# Mikrolysreklamen.net
KiCad netlist of a schematic drawn in Altium Designer
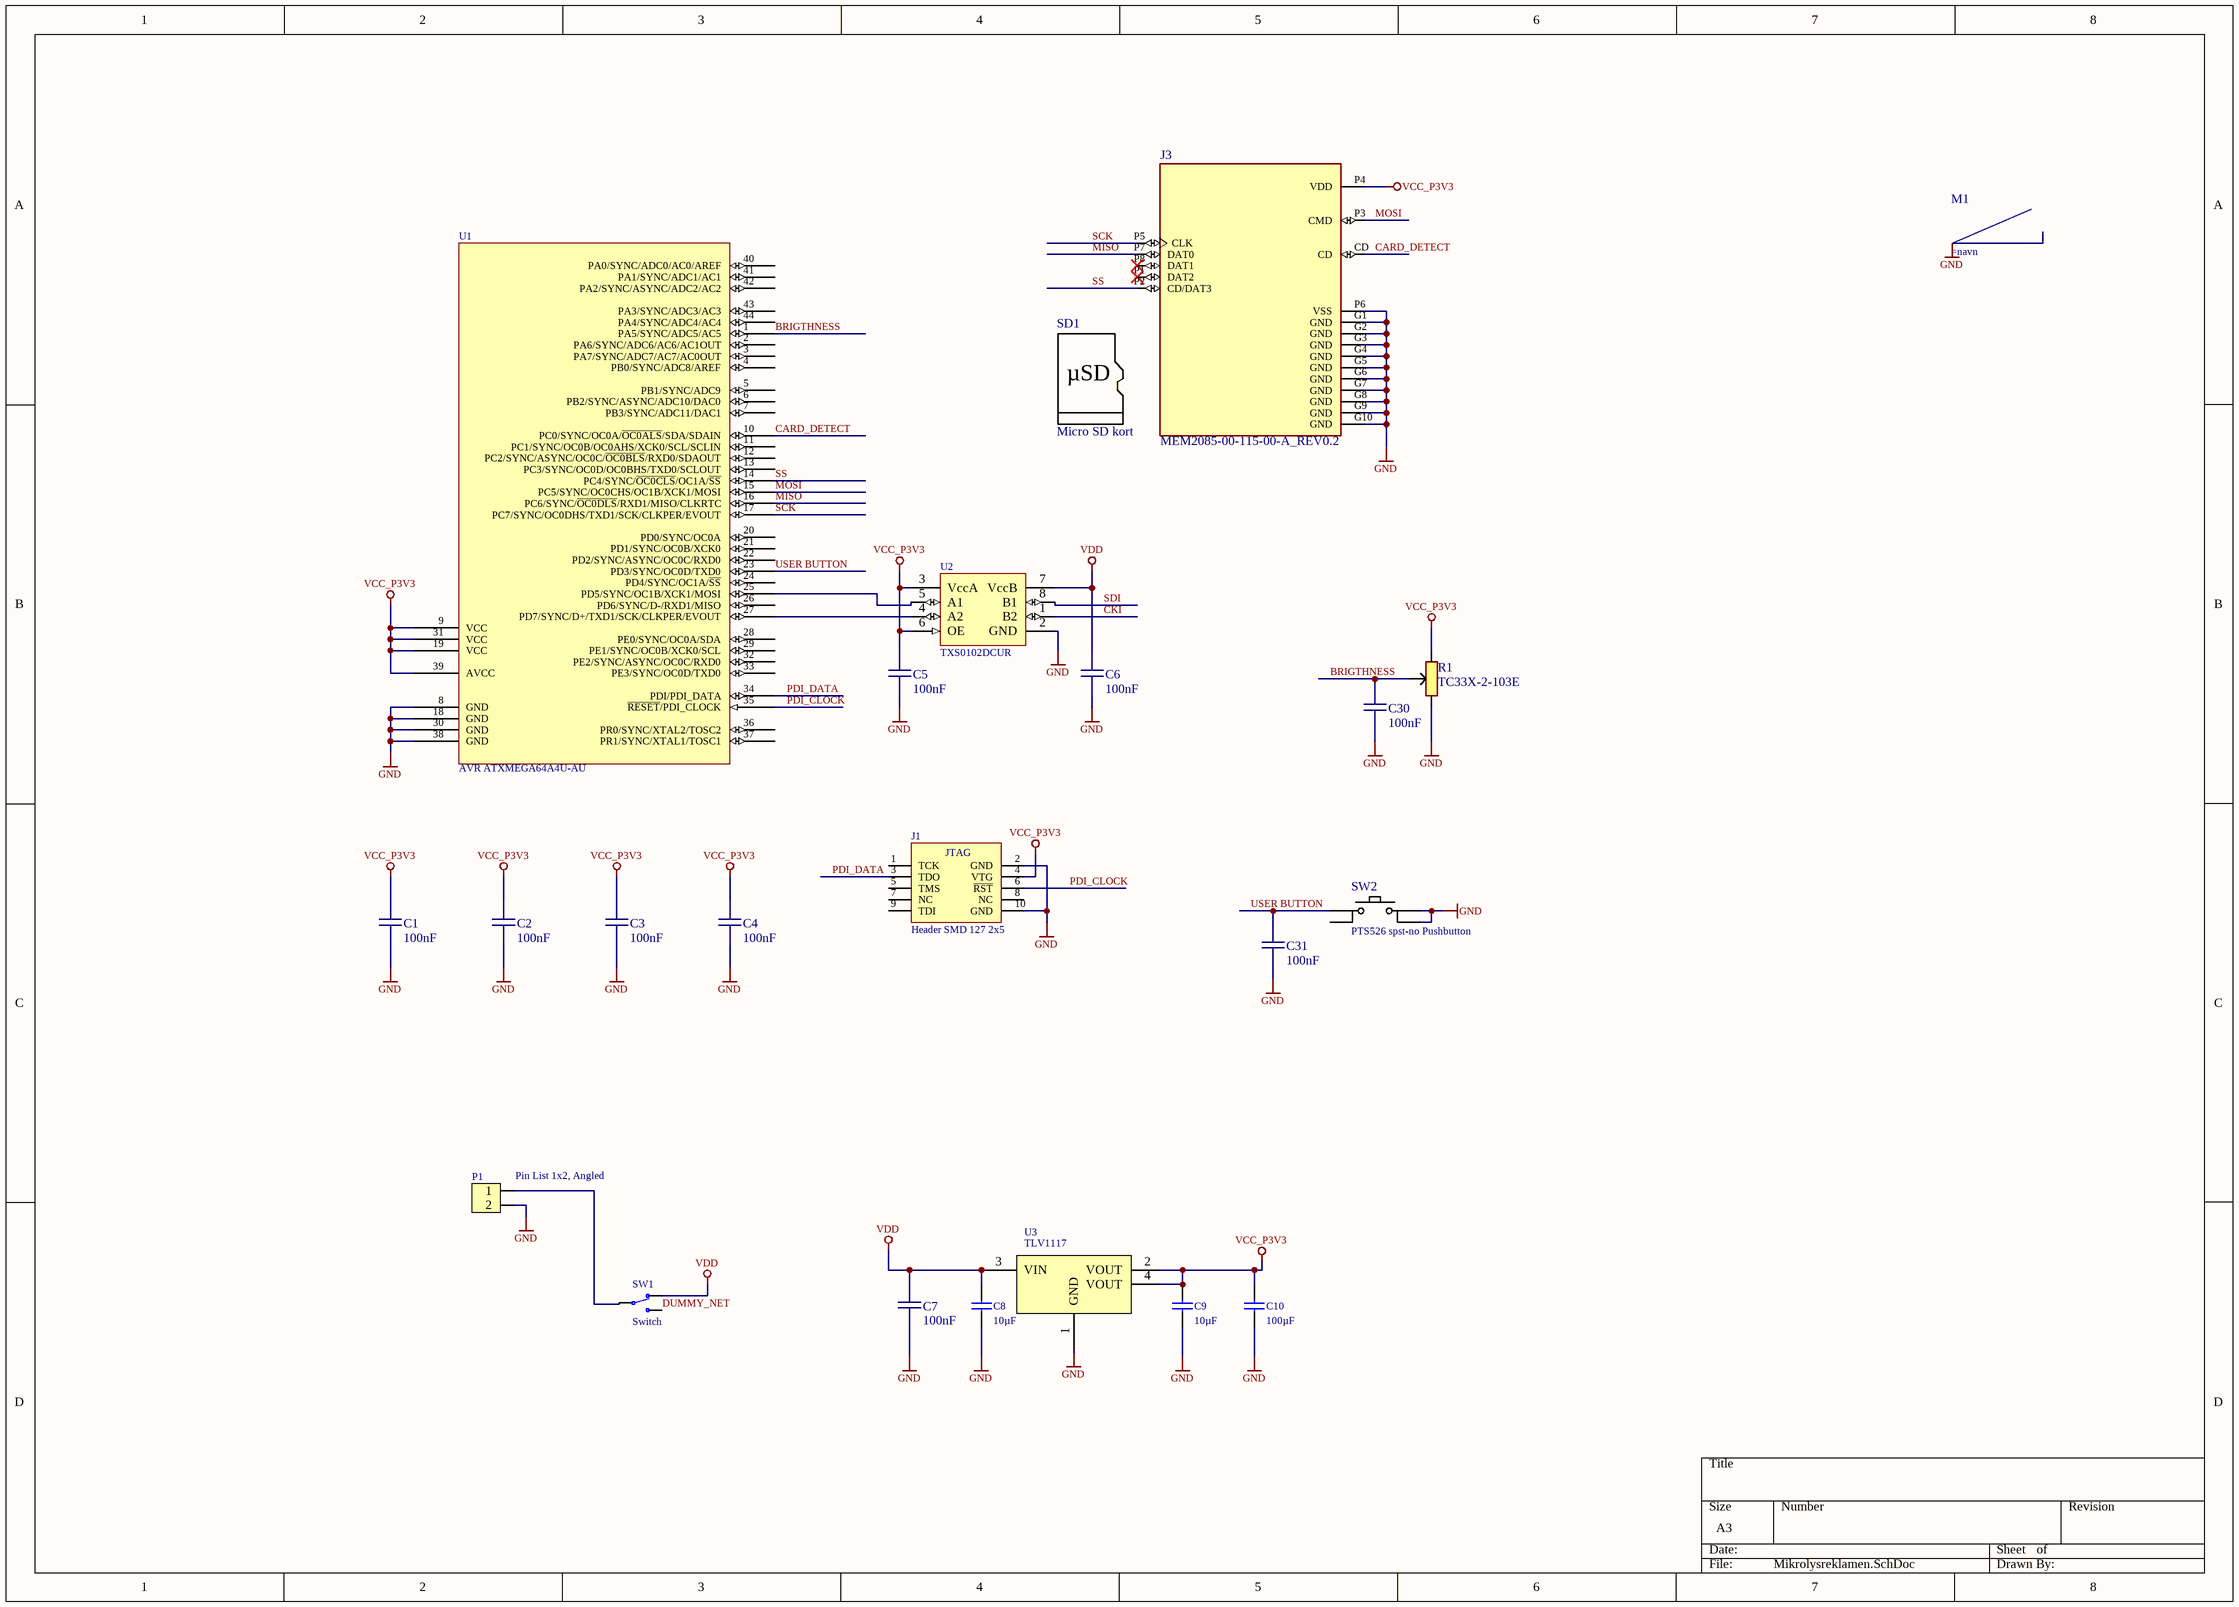
[diagram p0: Mikrolysreklamen.SchDoc]

(export (version "E")
  (design (tool "Eeschema 10.0.6"))
  (components
    (comp (ref "C1")
      (value "100nF")
      (footprint "CAPC0603(1608)55_N")
      (libsource (lib "OVLib_64") (part "CAP"))
    )
    (comp (ref "C2")
      (value "100nF")
      (footprint "CAPC0603(1608)55_N")
      (libsource (lib "OVLib_64") (part "CAP"))
    )
    (comp (ref "C3")
      (value "100nF")
      (footprint "CAPC0603(1608)55_N")
      (libsource (lib "OVLib_64") (part "CAP"))
    )
    (comp (ref "C4")
      (value "100nF")
      (footprint "CAPC0603(1608)55_N")
      (libsource (lib "OVLib_64") (part "CAP"))
    )
    (comp (ref "C5")
      (value "100nF")
      (footprint "CAPC0603(1608)55_N")
      (libsource (lib "OVLib_64") (part "CAP"))
    )
    (comp (ref "C6")
      (value "100nF")
      (footprint "CAPC0603(1608)55_N")
      (libsource (lib "OVLib_64") (part "CAP"))
    )
    (comp (ref "C7")
      (value "100nF")
      (footprint "CAPC0603(1608)55_N")
      (libsource (lib "OVLib_64") (part "CAP"))
    )
    (comp (ref "C8")
      (value "10µF")
      (footprint "CAPC1608X06L")
      (description "Capacitor, X5R, ±20%")
      (fields (field (name "PART NUMBER") "C0603-10µ") (field (name "PUBLISHER") "Nordic Semiconductor"))
      (libsource (lib "Nordic Passive DB") (part "CAP"))
    )
    (comp (ref "C9")
      (value "10µF")
      (footprint "CAPC1608X06L")
      (description "Capacitor, X5R, ±20%")
      (fields (field (name "PART NUMBER") "C0603-10µ") (field (name "PUBLISHER") "Nordic Semiconductor"))
      (libsource (lib "Nordic Passive DB") (part "CAP"))
    )
    (comp (ref "C10")
      (value "100µF")
      (footprint "CAPC2012X11L")
      (description "Chip Cap 0805")
      (fields (field (name "PART NUMBER") "C0805-TBD") (field (name "PUBLISHER") "Nordic Semiconductor"))
      (libsource (lib "Nordic Passive DB") (part "CAP"))
    )
    (comp (ref "C30")
      (value "100nF")
      (footprint "CAPC0603(1608)55_N")
      (libsource (lib "OVLib_64") (part "CAP"))
    )
    (comp (ref "C31")
      (value "100nF")
      (footprint "CAPC0603(1608)55_N")
      (libsource (lib "OVLib_64") (part "CAP"))
    )
    (comp (ref "J1")
      (value "Header SMD 127 2x5")
      (footprint "SMDHDRV10P127_2X5_615X330X560B")
      (description "1,27mm Pitch SMD Header")
      (libsource (lib "OVLib") (part "AVRJTAG"))
    )
    (comp (ref "J3")
      (value "MEM2085-00-115-00-A_REV0.2")
      (footprint "GCT_MEM2085-00-115-00-A_REV0.2")
      (description "MicroSD Push pull Memory Card Connector")
      (fields (field (name "MP") "MEM2085-00-115-00-A") (field (name "MF") "Global Connector Technology"))
      (libsource (lib "OVLib_64") (part "MEM2085-00-115-00-A_REV0.2"))
    )
    (comp (ref "M1")
      (value "~")
      (footprint "Imponatornaal_liten")
      (libsource (lib "Imponatornaal") (part "Imponatornaal"))
    )
    (comp (ref "P1")
      (value "Pin List 1x2, Angled")
      (footprint "LIST_ANG_1x2-SMD-2.54MM")
      (description "Pin List 1x2, 2.54mm (100mil), Right Angled, SMD")
      (fields
        (field (name "PART NUMBER") "Pin List Ang 1x2 SMD, 2.54mm")
        (field (name "MANUFACTURER") "W-CON")
        (field (name "PUBLISHER") "Nordic Semiconductor")
      )
      (libsource (lib "Nordic Passive DB") (part "CONN-2"))
    )
    (comp (ref "R1")
      (value "TC33X-2-103E")
      (footprint "TRIM_TC33X-2-103E")
      (libsource (lib "OVLib_64") (part "Potmeter"))
    )
    (comp (ref "SD1")
      (value "Micro SD kort")
      (footprint "microsdcard")
      (libsource (lib "OVLib_64") (part "microsdcard"))
    )
    (comp (ref "SW1")
      (value "Switch")
      (footprint "JS102011SAQN")
      (description "SMD slide Switch (ON-ON)")
      (fields
        (field (name "PART NUMBER") "JS102011SAQN")
        (field (name "MANUFACTURER") "C&K Components")
        (field (name "PUBLISHER") "Nordic Semiconductor")
      )
      (libsource (lib "Nordic Discrete DB") (part "SW-SPDT"))
    )
    (comp (ref "SW2")
      (value "PTS526 spst-no Pushbutton")
      (footprint "PTS526_SK15_SMTR2_LFS")
      (libsource (lib "OVLib_64") (part "Pushbutton"))
    )
    (comp (ref "U1")
      (value "AVR ATXMEGA64A4U-AU")
      (footprint "TQFP80P1200X1200X120-44N")
      (description "Mikrokontroller")
      (libsource (lib "OVLib") (part "ATXMEGA-A4U"))
    )
    (comp (ref "U2")
      (value "TXS0102DCUR")
      (footprint "TSSOP50P310X90-8N")
      (description "IC VOLT-LEVEL TRANSLATOR 8-US8")
      (fields
        (field (name "MANUFACTURER") "Texas Instruments")
        (field (name "PUBLISHER") "Nordic Semiconductor")
      )
      (libsource (lib "Nordic Active DB") (part "TXS0102DC"))
    )
    (comp (ref "U3")
      (value "TLV1117")
      (footprint "SOT230P700X180-4N")
      (description "REG LDO 3.3V 0.8A SOT223")
      (fields
        (field (name "PART NUMBER") "TLV1117-33CDCYR")
        (field (name "MANUFACTURER") "Texas Instruments")
        (field (name "PUBLISHER") "Nordic Semiconductor")
      )
      (libsource (lib "Nordic Active DB") (part "LD1117_fixed"))
    )
  )
  (nets
    (net (code "1") (name "/BRIGTHNESS") (class "Default")
      (node (ref "C30") (pin "2") (pinfunction "2_2") (pintype "passive"))
      (node (ref "R1") (pin "2") (pinfunction "2_2") (pintype "passive"))
      (node (ref "U1") (pin "1") (pinfunction "PA5/SYNC/ADC5/AC5_1") (pintype "bidirectional"))
    )
    (net (code "2") (name "/CARD_DETECT") (class "Default")
      (node (ref "J3") (pin "CD") (pinfunction "CD_CD") (pintype "bidirectional"))
      (node (ref "U1") (pin "10") (pinfunction "PC0/SYNC/OC0A/~{OC0ALS}/SDA/SDAIN_10") (pintype "bidirectional"))
    )
    (net (code "3") (name "/CKI") (class "Default")
      (node (ref "U2") (pin "1") (pinfunction "B2_1") (pintype "bidirectional"))
    )
    (net (code "4") (name "/DUMMY_NET") (class "Default")
      (node (ref "SW1") (pin "3") (pinfunction "N.O_3") (pintype "passive"))
    )
    (net (code "5") (name "/MISO") (class "Default")
      (node (ref "J3") (pin "P7") (pinfunction "DAT0_P7") (pintype "bidirectional"))
      (node (ref "U1") (pin "16") (pinfunction "PC6/SYNC/~{OC0DLS}/RXD1/MISO/CLKRTC_16") (pintype "bidirectional"))
    )
    (net (code "6") (name "/MOSI") (class "Default")
      (node (ref "J3") (pin "P3") (pinfunction "CMD_P3") (pintype "bidirectional"))
      (node (ref "U1") (pin "15") (pinfunction "PC5/SYNC/OC0CHS/OC1B/XCK1/MOSI_15") (pintype "bidirectional"))
    )
    (net (code "7") (name "/PDI_CLOCK") (class "Default")
      (node (ref "J1") (pin "6") (pinfunction "~{RST}_6") (pintype "passive"))
      (node (ref "U1") (pin "35") (pinfunction "~{RESET}/PDI_CLOCK_35") (pintype "input"))
    )
    (net (code "8") (name "/PDI_DATA") (class "Default")
      (node (ref "J1") (pin "3") (pinfunction "TDO_3") (pintype "passive"))
      (node (ref "U1") (pin "34") (pinfunction "PDI/PDI_DATA_34") (pintype "bidirectional"))
    )
    (net (code "9") (name "/SCK") (class "Default")
      (node (ref "J3") (pin "P5") (pinfunction "CLK_P5") (pintype "bidirectional"))
      (node (ref "U1") (pin "17") (pinfunction "PC7/SYNC/OC0DHS/TXD1/SCK/CLKPER/EVOUT_17") (pintype "bidirectional"))
    )
    (net (code "10") (name "/SDI") (class "Default")
      (node (ref "U2") (pin "8") (pinfunction "B1_8") (pintype "bidirectional"))
    )
    (net (code "11") (name "/SS") (class "Default")
      (node (ref "J3") (pin "P2") (pinfunction "CD/DAT3_P2") (pintype "bidirectional"))
      (node (ref "U1") (pin "14") (pinfunction "PC4/SYNC/~{OC0CLS}/OC1A/~{SS}_14") (pintype "bidirectional"))
    )
    (net (code "12") (name "/USER BUTTON") (class "Default")
      (node (ref "C31") (pin "2") (pinfunction "2_2") (pintype "passive"))
      (node (ref "SW2") (pin "1") (pinfunction "1_1") (pintype "passive"))
      (node (ref "U1") (pin "23") (pinfunction "PD3/SYNC/OC0D/TXD0_23") (pintype "bidirectional"))
    )
    (net (code "13") (name "GND") (class "Default")
      (node (ref "C1") (pin "1") (pinfunction "1_1") (pintype "passive"))
      (node (ref "C10") (pin "1") (pinfunction "1_1") (pintype "passive"))
      (node (ref "C2") (pin "1") (pinfunction "1_1") (pintype "passive"))
      (node (ref "C3") (pin "1") (pinfunction "1_1") (pintype "passive"))
      (node (ref "C30") (pin "1") (pinfunction "1_1") (pintype "passive"))
      (node (ref "C31") (pin "1") (pinfunction "1_1") (pintype "passive"))
      (node (ref "C4") (pin "1") (pinfunction "1_1") (pintype "passive"))
      (node (ref "C5") (pin "1") (pinfunction "1_1") (pintype "passive"))
      (node (ref "C6") (pin "1") (pinfunction "1_1") (pintype "passive"))
      (node (ref "C7") (pin "1") (pinfunction "1_1") (pintype "passive"))
      (node (ref "C8") (pin "1") (pinfunction "1_1") (pintype "passive"))
      (node (ref "C9") (pin "1") (pinfunction "1_1") (pintype "passive"))
      (node (ref "J1") (pin "10") (pinfunction "GND_10") (pintype "passive"))
      (node (ref "J1") (pin "2") (pinfunction "GND_2") (pintype "passive"))
      (node (ref "J3") (pin "G1") (pinfunction "GND_G1") (pintype "power_in"))
      (node (ref "J3") (pin "G10") (pinfunction "GND_G10") (pintype "power_in"))
      (node (ref "J3") (pin "G2") (pinfunction "GND_G2") (pintype "power_in"))
      (node (ref "J3") (pin "G3") (pinfunction "GND_G3") (pintype "power_in"))
      (node (ref "J3") (pin "G4") (pinfunction "GND_G4") (pintype "power_in"))
      (node (ref "J3") (pin "G5") (pinfunction "GND_G5") (pintype "power_in"))
      (node (ref "J3") (pin "G6") (pinfunction "GND_G6") (pintype "power_in"))
      (node (ref "J3") (pin "G7") (pinfunction "GND_G7") (pintype "power_in"))
      (node (ref "J3") (pin "G8") (pinfunction "GND_G8") (pintype "power_in"))
      (node (ref "J3") (pin "G9") (pinfunction "GND_G9") (pintype "power_in"))
      (node (ref "J3") (pin "P6") (pinfunction "VSS_P6") (pintype "power_in"))
      (node (ref "M1") (pin "0") (pinfunction "0_0") (pintype "passive"))
      (node (ref "P1") (pin "2") (pinfunction "2_2") (pintype "passive"))
      (node (ref "R1") (pin "1") (pinfunction "1_1") (pintype "passive"))
      (node (ref "SW2") (pin "3") (pinfunction "3_3") (pintype "passive"))
      (node (ref "SW2") (pin "4") (pinfunction "4_4") (pintype "passive"))
      (node (ref "U1") (pin "18") (pinfunction "GND_18") (pintype "power_in"))
      (node (ref "U1") (pin "30") (pinfunction "GND_30") (pintype "power_in"))
      (node (ref "U1") (pin "38") (pinfunction "GND_38") (pintype "power_in"))
      (node (ref "U1") (pin "8") (pinfunction "GND_8") (pintype "power_in"))
      (node (ref "U2") (pin "2") (pinfunction "GND_2") (pintype "power_in"))
      (node (ref "U3") (pin "1") (pinfunction "GND_1") (pintype "power_in"))
    )
    (net (code "14") (name "Net-(SW1-COM)") (class "Default")
      (node (ref "P1") (pin "1") (pinfunction "1_1") (pintype "passive"))
      (node (ref "SW1") (pin "2") (pinfunction "COM_2") (pintype "passive"))
    )
    (net (code "15") (name "Net-(U1-PD5{slash}SYNC{slash}OC1B{slash}XCK1{slash}MOSI)") (class "Default")
      (node (ref "U1") (pin "25") (pinfunction "PD5/SYNC/OC1B/XCK1/MOSI_25") (pintype "bidirectional"))
      (node (ref "U2") (pin "5") (pinfunction "A1_5") (pintype "bidirectional"))
    )
    (net (code "16") (name "Net-(U1-PD7{slash}SYNC{slash}D+{slash}TXD1{slash}SCK{slash}CLKPER{slash}EVOUT)") (class "Default")
      (node (ref "U1") (pin "27") (pinfunction "PD7/SYNC/D+/TXD1/SCK/CLKPER/EVOUT_27") (pintype "bidirectional"))
      (node (ref "U2") (pin "4") (pinfunction "A2_4") (pintype "bidirectional"))
    )
    (net (code "17") (name "VCC_P3V3") (class "Default")
      (node (ref "C1") (pin "2") (pinfunction "2_2") (pintype "passive"))
      (node (ref "C10") (pin "2") (pinfunction "2_2") (pintype "passive"))
      (node (ref "C2") (pin "2") (pinfunction "2_2") (pintype "passive"))
      (node (ref "C3") (pin "2") (pinfunction "2_2") (pintype "passive"))
      (node (ref "C4") (pin "2") (pinfunction "2_2") (pintype "passive"))
      (node (ref "C5") (pin "2") (pinfunction "2_2") (pintype "passive"))
      (node (ref "C9") (pin "2") (pinfunction "2_2") (pintype "passive"))
      (node (ref "J1") (pin "4") (pinfunction "VTG_4") (pintype "passive"))
      (node (ref "J3") (pin "P4") (pinfunction "VDD_P4") (pintype "power_in"))
      (node (ref "R1") (pin "3") (pinfunction "3_3") (pintype "passive"))
      (node (ref "U1") (pin "19") (pinfunction "VCC_19") (pintype "power_in"))
      (node (ref "U1") (pin "31") (pinfunction "VCC_31") (pintype "power_in"))
      (node (ref "U1") (pin "39") (pinfunction "AVCC_39") (pintype "power_in"))
      (node (ref "U1") (pin "9") (pinfunction "VCC_9") (pintype "power_in"))
      (node (ref "U2") (pin "3") (pinfunction "VccA_3") (pintype "power_in"))
      (node (ref "U2") (pin "6") (pinfunction "OE_6") (pintype "input"))
      (node (ref "U3") (pin "2") (pinfunction "VOUT_2") (pintype "power_in"))
      (node (ref "U3") (pin "4") (pinfunction "VOUT_4") (pintype "power_in"))
    )
    (net (code "18") (name "VDD") (class "Default")
      (node (ref "C6") (pin "2") (pinfunction "2_2") (pintype "passive"))
      (node (ref "C7") (pin "2") (pinfunction "2_2") (pintype "passive"))
      (node (ref "C8") (pin "2") (pinfunction "2_2") (pintype "passive"))
      (node (ref "SW1") (pin "1") (pinfunction "N.C_1") (pintype "passive"))
      (node (ref "U2") (pin "7") (pinfunction "VccB_7") (pintype "power_in"))
      (node (ref "U3") (pin "3") (pinfunction "VIN_3") (pintype "power_in"))
    )
    (net (code "19") (name "unconnected-(J1-NC-Pad7)") (class "Default")
      (node (ref "J1") (pin "7") (pinfunction "NC_7") (pintype "passive"))
    )
    (net (code "20") (name "unconnected-(J1-NC-Pad8)") (class "Default")
      (node (ref "J1") (pin "8") (pinfunction "NC_8") (pintype "passive"))
    )
    (net (code "21") (name "unconnected-(J1-TCK-Pad1)") (class "Default")
      (node (ref "J1") (pin "1") (pinfunction "TCK_1") (pintype "passive"))
    )
    (net (code "22") (name "unconnected-(J1-TDI-Pad9)") (class "Default")
      (node (ref "J1") (pin "9") (pinfunction "TDI_9") (pintype "passive"))
    )
    (net (code "23") (name "unconnected-(J1-TMS-Pad5)") (class "Default")
      (node (ref "J1") (pin "5") (pinfunction "TMS_5") (pintype "passive"))
    )
    (net (code "24") (name "unconnected-(J3-DAT1-PadP8)") (class "Default")
      (node (ref "J3") (pin "P8") (pinfunction "DAT1_P8") (pintype "bidirectional+no_connect"))
    )
    (net (code "25") (name "unconnected-(J3-DAT2-PadP1)") (class "Default")
      (node (ref "J3") (pin "P1") (pinfunction "DAT2_P1") (pintype "bidirectional+no_connect"))
    )
    (net (code "26") (name "unconnected-(SW2-Pad2)") (class "Default")
      (node (ref "SW2") (pin "2") (pinfunction "2_2") (pintype "passive"))
    )
    (net (code "27") (name "unconnected-(U1-PA0{slash}SYNC{slash}ADC0{slash}AC0{slash}AREF-Pad40)") (class "Default")
      (node (ref "U1") (pin "40") (pinfunction "PA0/SYNC/ADC0/AC0/AREF_40") (pintype "bidirectional"))
    )
    (net (code "28") (name "unconnected-(U1-PA1{slash}SYNC{slash}ADC1{slash}AC1-Pad41)") (class "Default")
      (node (ref "U1") (pin "41") (pinfunction "PA1/SYNC/ADC1/AC1_41") (pintype "bidirectional"))
    )
    (net (code "29") (name "unconnected-(U1-PA2{slash}SYNC{slash}ASYNC{slash}ADC2{slash}AC2-Pad42)") (class "Default")
      (node (ref "U1") (pin "42") (pinfunction "PA2/SYNC/ASYNC/ADC2/AC2_42") (pintype "bidirectional"))
    )
    (net (code "30") (name "unconnected-(U1-PA3{slash}SYNC{slash}ADC3{slash}AC3-Pad43)") (class "Default")
      (node (ref "U1") (pin "43") (pinfunction "PA3/SYNC/ADC3/AC3_43") (pintype "bidirectional"))
    )
    (net (code "31") (name "unconnected-(U1-PA4{slash}SYNC{slash}ADC4{slash}AC4-Pad44)") (class "Default")
      (node (ref "U1") (pin "44") (pinfunction "PA4/SYNC/ADC4/AC4_44") (pintype "bidirectional"))
    )
    (net (code "32") (name "unconnected-(U1-PA6{slash}SYNC{slash}ADC6{slash}AC6{slash}AC1OUT-Pad2)") (class "Default")
      (node (ref "U1") (pin "2") (pinfunction "PA6/SYNC/ADC6/AC6/AC1OUT_2") (pintype "bidirectional"))
    )
    (net (code "33") (name "unconnected-(U1-PA7{slash}SYNC{slash}ADC7{slash}AC7{slash}AC0OUT-Pad3)") (class "Default")
      (node (ref "U1") (pin "3") (pinfunction "PA7/SYNC/ADC7/AC7/AC0OUT_3") (pintype "bidirectional"))
    )
    (net (code "34") (name "unconnected-(U1-PB0{slash}SYNC{slash}ADC8{slash}AREF-Pad4)") (class "Default")
      (node (ref "U1") (pin "4") (pinfunction "PB0/SYNC/ADC8/AREF_4") (pintype "bidirectional"))
    )
    (net (code "35") (name "unconnected-(U1-PB1{slash}SYNC{slash}ADC9-Pad5)") (class "Default")
      (node (ref "U1") (pin "5") (pinfunction "PB1/SYNC/ADC9_5") (pintype "bidirectional"))
    )
    (net (code "36") (name "unconnected-(U1-PB2{slash}SYNC{slash}ASYNC{slash}ADC10{slash}DAC0-Pad6)") (class "Default")
      (node (ref "U1") (pin "6") (pinfunction "PB2/SYNC/ASYNC/ADC10/DAC0_6") (pintype "bidirectional"))
    )
    (net (code "37") (name "unconnected-(U1-PB3{slash}SYNC{slash}ADC11{slash}DAC1-Pad7)") (class "Default")
      (node (ref "U1") (pin "7") (pinfunction "PB3/SYNC/ADC11/DAC1_7") (pintype "bidirectional"))
    )
    (net (code "38") (name "unconnected-(U1-PC1{slash}SYNC{slash}OC0B{slash}OC0AHS{slash}XCK0{slash}SCL{slash}SCLIN-Pad11)") (class "Default")
      (node (ref "U1") (pin "11") (pinfunction "PC1/SYNC/OC0B/OC0AHS/XCK0/SCL/SCLIN_11") (pintype "bidirectional"))
    )
    (net (code "39") (name "unconnected-(U1-PC2{slash}SYNC{slash}ASYNC{slash}OC0C{slash}~{OC0BLS}{slash}RXD0{slash}SDAOUT-Pad12)") (class "Default")
      (node (ref "U1") (pin "12") (pinfunction "PC2/SYNC/ASYNC/OC0C/~{OC0BLS}/RXD0/SDAOUT_12") (pintype "bidirectional"))
    )
    (net (code "40") (name "unconnected-(U1-PC3{slash}SYNC{slash}OC0D{slash}OC0BHS{slash}TXD0{slash}SCLOUT-Pad13)") (class "Default")
      (node (ref "U1") (pin "13") (pinfunction "PC3/SYNC/OC0D/OC0BHS/TXD0/SCLOUT_13") (pintype "bidirectional"))
    )
    (net (code "41") (name "unconnected-(U1-PD0{slash}SYNC{slash}OC0A-Pad20)") (class "Default")
      (node (ref "U1") (pin "20") (pinfunction "PD0/SYNC/OC0A_20") (pintype "bidirectional"))
    )
    (net (code "42") (name "unconnected-(U1-PD1{slash}SYNC{slash}OC0B{slash}XCK0-Pad21)") (class "Default")
      (node (ref "U1") (pin "21") (pinfunction "PD1/SYNC/OC0B/XCK0_21") (pintype "bidirectional"))
    )
    (net (code "43") (name "unconnected-(U1-PD2{slash}SYNC{slash}ASYNC{slash}OC0C{slash}RXD0-Pad22)") (class "Default")
      (node (ref "U1") (pin "22") (pinfunction "PD2/SYNC/ASYNC/OC0C/RXD0_22") (pintype "bidirectional"))
    )
    (net (code "44") (name "unconnected-(U1-PD4{slash}SYNC{slash}OC1A{slash}~{SS}-Pad24)") (class "Default")
      (node (ref "U1") (pin "24") (pinfunction "PD4/SYNC/OC1A/~{SS}_24") (pintype "bidirectional"))
    )
    (net (code "45") (name "unconnected-(U1-PD6{slash}SYNC{slash}D-{slash}RXD1{slash}MISO-Pad26)") (class "Default")
      (node (ref "U1") (pin "26") (pinfunction "PD6/SYNC/D-/RXD1/MISO_26") (pintype "bidirectional"))
    )
    (net (code "46") (name "unconnected-(U1-PE0{slash}SYNC{slash}OC0A{slash}SDA-Pad28)") (class "Default")
      (node (ref "U1") (pin "28") (pinfunction "PE0/SYNC/OC0A/SDA_28") (pintype "bidirectional"))
    )
    (net (code "47") (name "unconnected-(U1-PE1{slash}SYNC{slash}OC0B{slash}XCK0{slash}SCL-Pad29)") (class "Default")
      (node (ref "U1") (pin "29") (pinfunction "PE1/SYNC/OC0B/XCK0/SCL_29") (pintype "bidirectional"))
    )
    (net (code "48") (name "unconnected-(U1-PE2{slash}SYNC{slash}ASYNC{slash}OC0C{slash}RXD0-Pad32)") (class "Default")
      (node (ref "U1") (pin "32") (pinfunction "PE2/SYNC/ASYNC/OC0C/RXD0_32") (pintype "bidirectional"))
    )
    (net (code "49") (name "unconnected-(U1-PE3{slash}SYNC{slash}OC0D{slash}TXD0-Pad33)") (class "Default")
      (node (ref "U1") (pin "33") (pinfunction "PE3/SYNC/OC0D/TXD0_33") (pintype "bidirectional"))
    )
    (net (code "50") (name "unconnected-(U1-PR0{slash}SYNC{slash}XTAL2{slash}TOSC2-Pad36)") (class "Default")
      (node (ref "U1") (pin "36") (pinfunction "PR0/SYNC/XTAL2/TOSC2_36") (pintype "bidirectional"))
    )
    (net (code "51") (name "unconnected-(U1-PR1{slash}SYNC{slash}XTAL1{slash}TOSC1-Pad37)") (class "Default")
      (node (ref "U1") (pin "37") (pinfunction "PR1/SYNC/XTAL1/TOSC1_37") (pintype "bidirectional"))
    )
  )
)
